# Relay_Module_V1.net
KiCad netlist of a schematic drawn in EAGLE
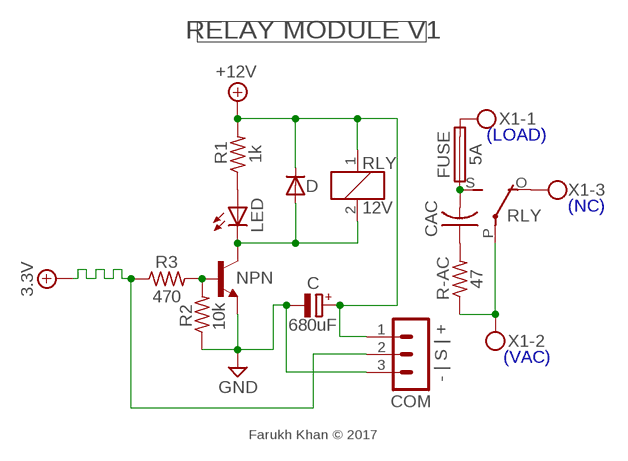
[diagram p0: schematic, sheet 1]

(export (version "E")
  (design (tool "Eeschema 10.0.6"))
  (components
    (comp (ref "C")
      (value "680uF")
      (footprint "eagle-import:E3,5-10")
      (libsource (lib "eagle-import") (part "CPOL-EUE3.5-10"))
    )
    (comp (ref "CAC")
      (value "C-US150-064X183")
      (footprint "eagle-import:C150-064X183")
      (libsource (lib "eagle-import") (part "C-US150-064X183"))
    )
    (comp (ref "COM")
      (value "- | S | +")
      (footprint "eagle-import:MA03-1")
      (libsource (lib "eagle-import") (part "MA03-1"))
    )
    (comp (ref "D")
      (value "1N4004")
      (footprint "eagle-import:DO41-10")
      (libsource (lib "eagle-import") (part "1N4004"))
    )
    (comp (ref "FUSE")
      (value "5A")
      (footprint "eagle-import:SH22")
      (libsource (lib "eagle-import") (part "SH22"))
    )
    (comp (ref "LED")
      (value "LED3MM")
      (footprint "eagle-import:LED3MM")
      (libsource (lib "eagle-import") (part "LED3MM"))
    )
    (comp (ref "NPN")
      (value "2N2222A")
      (footprint "eagle-import:TO18")
      (libsource (lib "eagle-import") (part "2N2222A"))
    )
    (comp (ref "R-AC")
      (value "47")
      (footprint "eagle-import:0617_17")
      (libsource (lib "eagle-import") (part "R-US_0617/17"))
    )
    (comp (ref "R1")
      (value "1k")
      (footprint "eagle-import:0204_7")
      (libsource (lib "eagle-import") (part "R-US_0204/7"))
    )
    (comp (ref "R2")
      (value "10k")
      (footprint "eagle-import:0204_7")
      (libsource (lib "eagle-import") (part "R-US_0204/7"))
    )
    (comp (ref "R3")
      (value "470")
      (footprint "eagle-import:0204_7")
      (libsource (lib "eagle-import") (part "R-US_0204/7"))
    )
    (comp (ref "RLY")
      (value "12V")
      (footprint "eagle-import:G5LE")
      (libsource (lib "eagle-import") (part "G5LE"))
    )
    (comp (ref "X1")
      (value "MKDSN1,5/3-5,08")
      (footprint "eagle-import:MKDSN1,5_3-5,08")
      (libsource (lib "eagle-import") (part "MKDSN1,5/3-5,08"))
    )
  )
  (nets
    (net (code "1") (name "+12V") (class "Default")
      (node (ref "C") (pin "+") (pinfunction "+_+") (pintype "passive"))
      (node (ref "COM") (pin "1") (pinfunction "1_1") (pintype "passive"))
      (node (ref "D") (pin "C") (pinfunction "C_C") (pintype "passive"))
      (node (ref "R1") (pin "2") (pinfunction "2_2") (pintype "passive"))
      (node (ref "RLY") (pin "1") (pinfunction "1_1") (pintype "passive"))
    )
    (net (code "2") (name "3.3V") (class "Default")
      (node (ref "COM") (pin "2") (pinfunction "2_2") (pintype "passive"))
      (node (ref "R3") (pin "1") (pinfunction "1_1") (pintype "passive"))
    )
    (net (code "3") (name "GND") (class "Default")
      (node (ref "C") (pin "-") (pinfunction "-_-") (pintype "passive"))
      (node (ref "COM") (pin "3") (pinfunction "3_3") (pintype "passive"))
      (node (ref "NPN") (pin "1") (pinfunction "E_1") (pintype "passive"))
      (node (ref "R2") (pin "1") (pinfunction "1_1") (pintype "passive"))
    )
    (net (code "4") (name "Net-(CAC-Pad1)") (class "Default")
      (node (ref "CAC") (pin "1") (pinfunction "1_1") (pintype "passive"))
      (node (ref "R-AC") (pin "2") (pinfunction "2_2") (pintype "passive"))
    )
    (net (code "5") (name "Net-(CAC-Pad2)") (class "Default")
      (node (ref "CAC") (pin "2") (pinfunction "2_2") (pintype "passive"))
      (node (ref "FUSE") (pin "1") (pinfunction "1_1") (pintype "passive"))
      (node (ref "RLY") (pin "S") (pinfunction "S_S") (pintype "passive"))
    )
    (net (code "6") (name "Net-(LED-C)") (class "Default")
      (node (ref "D") (pin "A") (pinfunction "A_A") (pintype "passive"))
      (node (ref "LED") (pin "K") (pinfunction "C_K") (pintype "passive"))
      (node (ref "NPN") (pin "3") (pinfunction "C_3") (pintype "passive"))
      (node (ref "RLY") (pin "2") (pinfunction "2_2") (pintype "passive"))
    )
    (net (code "7") (name "Net-(LED-PadA)") (class "Default")
      (node (ref "LED") (pin "A") (pinfunction "A_A") (pintype "passive"))
      (node (ref "R1") (pin "1") (pinfunction "1_1") (pintype "passive"))
    )
    (net (code "8") (name "Net-(NPN-B)") (class "Default")
      (node (ref "NPN") (pin "2") (pinfunction "B_2") (pintype "passive"))
      (node (ref "R2") (pin "2") (pinfunction "2_2") (pintype "passive"))
      (node (ref "R3") (pin "2") (pinfunction "2_2") (pintype "passive"))
    )
    (net (code "9") (name "Net-(X1A-KL)") (class "Default")
      (node (ref "FUSE") (pin "2") (pinfunction "2_2") (pintype "passive"))
      (node (ref "X1") (pin "1") (pinfunction "KL_1") (pintype "passive"))
    )
    (net (code "10") (name "Net-(X1B-KL)") (class "Default")
      (node (ref "R-AC") (pin "1") (pinfunction "1_1") (pintype "passive"))
      (node (ref "RLY") (pin "P") (pinfunction "P_P") (pintype "passive"))
      (node (ref "X1") (pin "2") (pinfunction "KL_2") (pintype "passive"))
    )
    (net (code "11") (name "Net-(X1C-KL)") (class "Default")
      (node (ref "RLY") (pin "O") (pinfunction "O_O") (pintype "passive"))
      (node (ref "X1") (pin "3") (pinfunction "KL_3") (pintype "passive"))
    )
  )
)
